# RTC.net
KiCad netlist of a schematic drawn in Altium Designer
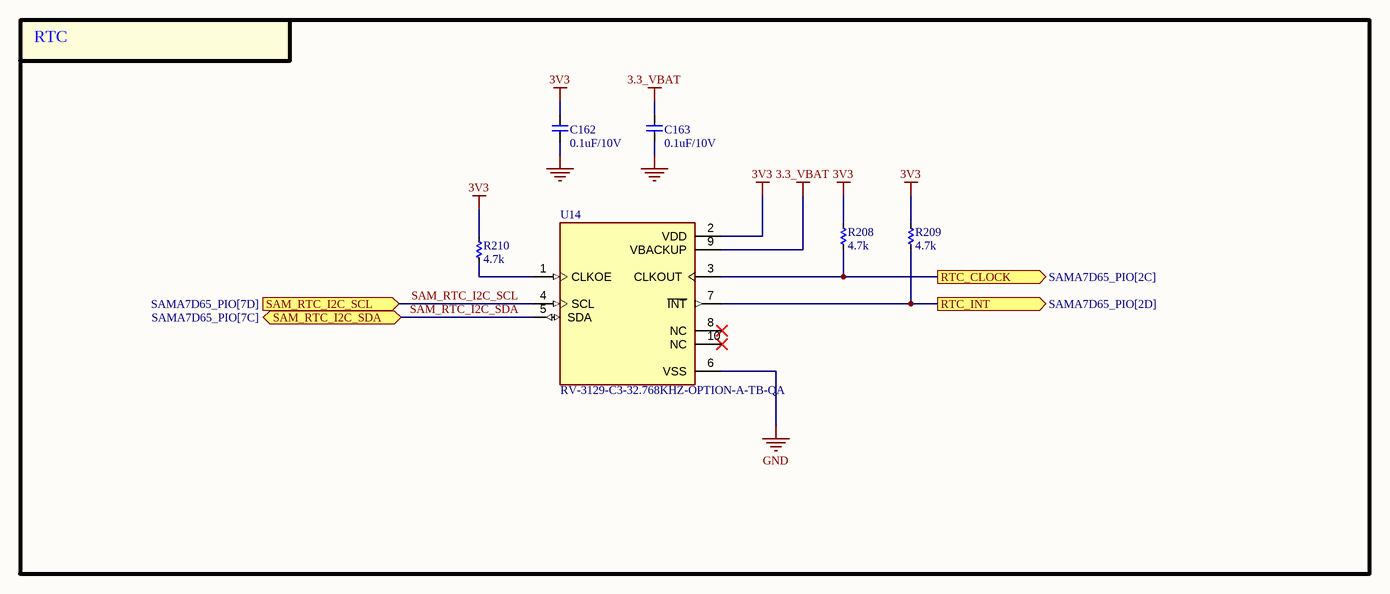
[diagram p0: RTC.SchDoc]

(export (version "E")
  (design (tool "Eeschema 10.0.6"))
  (components
    (comp (ref "C162")
      (value "0.1uF/10V")
      (footprint "CAP_C_1005X50_L")
      (description "CAP CHIP")
      (libsource (lib "IFBschelib") (part "_CAP_C_2"))
    )
    (comp (ref "C163")
      (value "0.1uF/10V")
      (footprint "CAP_C_1005X50_L")
      (description "CAP CHIP")
      (libsource (lib "IFBschelib") (part "_CAP_C_2"))
    )
    (comp (ref "R208")
      (value "4.7k")
      (footprint "RES_C_1005x30_L")
      (description "RES")
      (libsource (lib "IFBschelib") (part "_RES_B_2"))
    )
    (comp (ref "R209")
      (value "4.7k")
      (footprint "RES_C_1005x30_L")
      (description "RES")
      (libsource (lib "IFBschelib") (part "_RES_B_2"))
    )
    (comp (ref "R210")
      (value "4.7k")
      (footprint "RES_C_1005x30_L")
      (description "RES")
      (libsource (lib "IFBschelib") (part "_RES_B_2"))
    )
    (comp (ref "U14")
      (value "RV-3129-C3-32.768KHZ-OPTION-A-TB-QA")
      (footprint "IC_RV-3129-C3-32.768KHZ-OPTION-A-TB-QA")
      (description "Real-Time Clock Module with I2C-Bus")
      (libsource (lib "IFBschelib") (part "RV-3129-C3-32.768KHZ-OPTION-A-TB-QA"))
    )
  )
  (nets
    (net (code "1") (name "/RTC_CLOCK") (class "Default")
      (node (ref "R208") (pin "2") (pinfunction "2_2") (pintype "passive"))
      (node (ref "U14") (pin "3") (pinfunction "CLKOUT_3") (pintype "passive"))
    )
    (net (code "2") (name "/RTC_INT") (class "Default")
      (node (ref "R209") (pin "2") (pinfunction "2_2") (pintype "passive"))
      (node (ref "U14") (pin "7") (pinfunction "~{INT}_7") (pintype "output"))
    )
    (net (code "3") (name "/SAM_RTC_I2C_SCL") (class "Default")
      (node (ref "U14") (pin "4") (pinfunction "SCL_4") (pintype "input"))
    )
    (net (code "4") (name "/SAM_RTC_I2C_SDA") (class "Default")
      (node (ref "U14") (pin "5") (pinfunction "SDA_5") (pintype "bidirectional"))
    )
    (net (code "5") (name "3.3_VBAT") (class "Default")
      (node (ref "C163") (pin "2") (pinfunction "2_2") (pintype "passive"))
      (node (ref "U14") (pin "9") (pinfunction "VBACKUP_9") (pintype "power_in"))
    )
    (net (code "6") (name "3V3") (class "Default")
      (node (ref "C162") (pin "2") (pinfunction "2_2") (pintype "passive"))
      (node (ref "R208") (pin "1") (pinfunction "1_1") (pintype "passive"))
      (node (ref "R209") (pin "1") (pinfunction "1_1") (pintype "passive"))
      (node (ref "R210") (pin "1") (pinfunction "1_1") (pintype "passive"))
      (node (ref "U14") (pin "2") (pinfunction "VDD_2") (pintype "power_in"))
    )
    (net (code "7") (name "GND") (class "Default")
      (node (ref "C162") (pin "1") (pinfunction "1_1") (pintype "passive"))
      (node (ref "C163") (pin "1") (pinfunction "1_1") (pintype "passive"))
      (node (ref "U14") (pin "6") (pinfunction "VSS_6") (pintype "power_in"))
    )
    (net (code "8") (name "Net-(U14-CLKOE)") (class "Default")
      (node (ref "R210") (pin "2") (pinfunction "2_2") (pintype "passive"))
      (node (ref "U14") (pin "1") (pinfunction "CLKOE_1") (pintype "input"))
    )
    (net (code "9") (name "unconnected-(U14-NC-Pad8)") (class "Default")
      (node (ref "U14") (pin "8") (pinfunction "NC_8") (pintype "passive+no_connect"))
    )
    (net (code "10") (name "unconnected-(U14-NC-Pad10)") (class "Default")
      (node (ref "U14") (pin "10") (pinfunction "NC_10") (pintype "passive+no_connect"))
    )
  )
)
